# Micro.net
KiCad netlist of a schematic drawn in Altium Designer
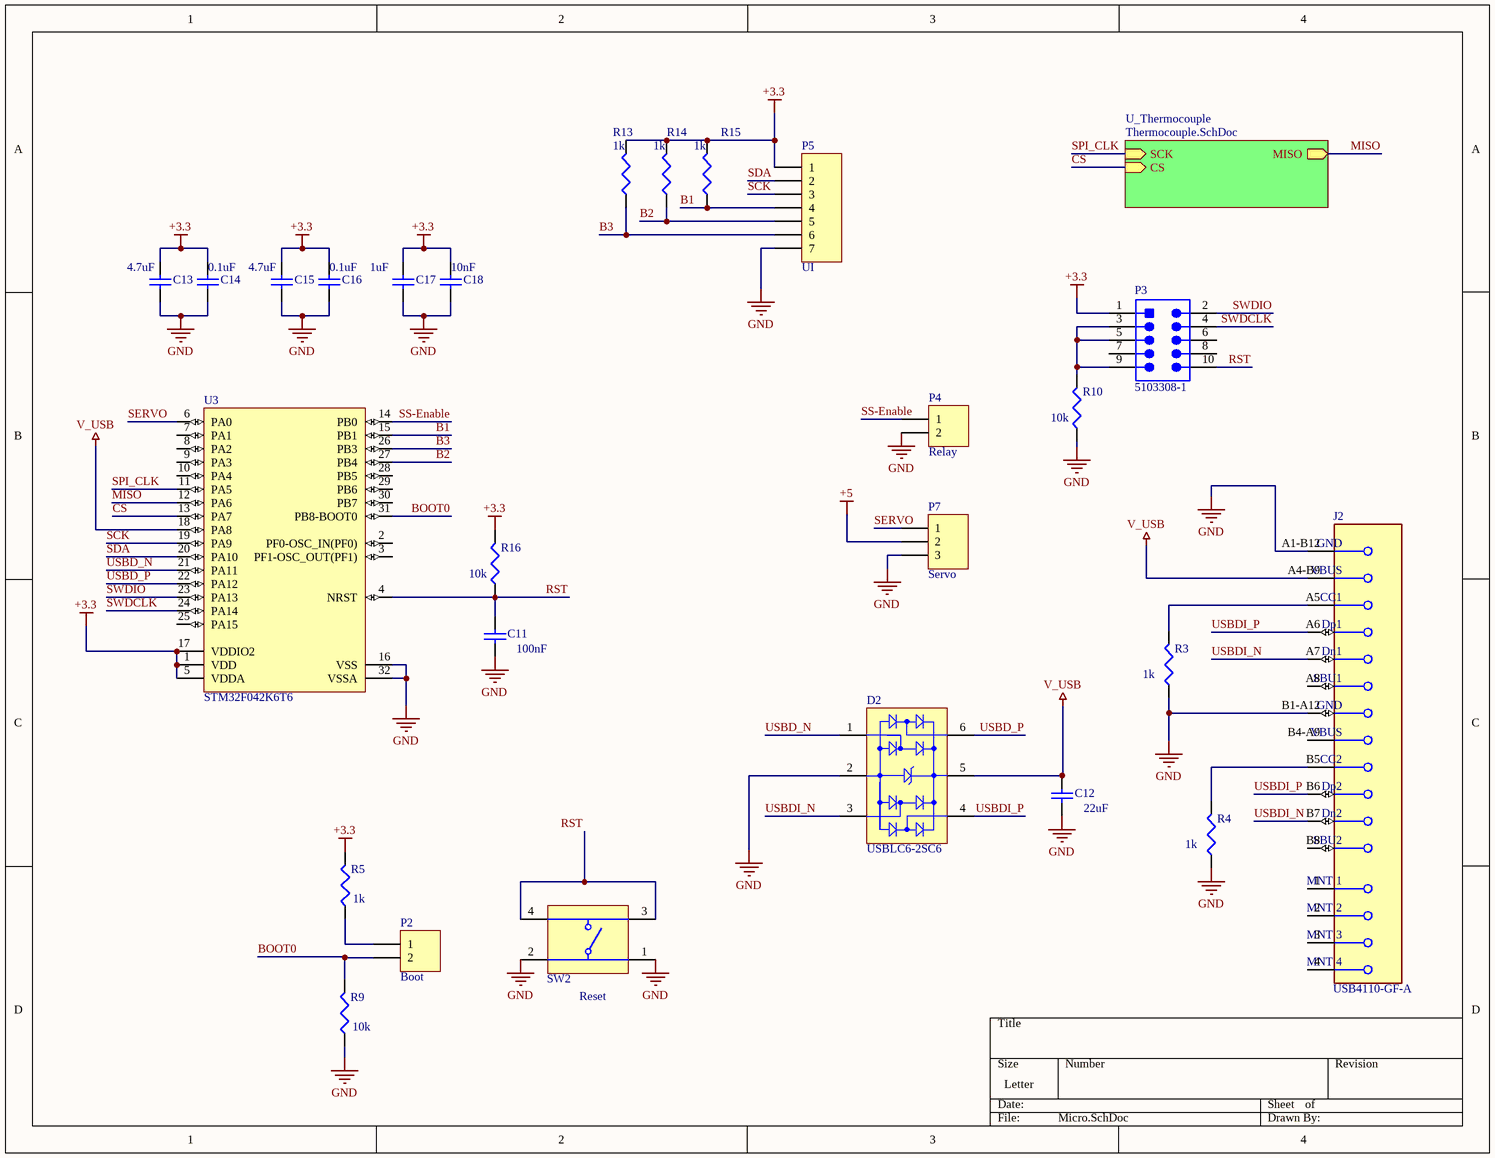
[diagram p0: Micro.SchDoc]

(export (version "E")
  (design (tool "Eeschema 10.0.6"))
  (components
    (comp (ref "C11")
      (value "100nF")
      (footprint "1608[0603]")
      (description "Capacitor (Semiconductor SIM Model)")
      (fields
        (field (name "LCSC PART #") "C14663")
        (field (name "Comment") "Cap Semi")
        (field (name "PUBLISHER") "Altium Limited")
      )
      (libsource (lib "STM32F4_Breakout") (part "Cap Semi_3"))
    )
    (comp (ref "C12")
      (value "22uF")
      (footprint "1608[0603]")
      (description "Capacitor (Semiconductor SIM Model)")
      (fields
        (field (name "LCSC PART #") "C14663")
        (field (name "Comment") "Cap Semi")
        (field (name "PUBLISHER") "Altium Limited")
      )
      (libsource (lib "STM32F4_Breakout") (part "Cap Semi_3"))
    )
    (comp (ref "C13")
      (value "4.7uF")
      (footprint "1608[0603]")
      (description "Capacitor (Semiconductor SIM Model)")
      (fields
        (field (name "LCSC PART #") "C15849")
        (field (name "Comment") "Cap Semi")
        (field (name "PUBLISHER") "Altium Limited")
      )
      (libsource (lib "STM32F4_Breakout") (part "Cap Semi_1"))
    )
    (comp (ref "C14")
      (value "0.1uF")
      (footprint "1608[0603]")
      (description "Capacitor (Semiconductor SIM Model)")
      (fields
        (field (name "LCSC PART #") "C15195")
        (field (name "Comment") "Cap Semi")
        (field (name "PUBLISHER") "Altium Limited")
      )
      (libsource (lib "STM32F4_Breakout") (part "Cap Semi_2"))
    )
    (comp (ref "C15")
      (value "4.7uF")
      (footprint "1608[0603]")
      (description "Capacitor (Semiconductor SIM Model)")
      (fields
        (field (name "LCSC PART #") "C15849")
        (field (name "Comment") "Cap Semi")
        (field (name "PUBLISHER") "Altium Limited")
      )
      (libsource (lib "STM32F4_Breakout") (part "Cap Semi_1"))
    )
    (comp (ref "C16")
      (value "0.1uF")
      (footprint "1608[0603]")
      (description "Capacitor (Semiconductor SIM Model)")
      (fields
        (field (name "LCSC PART #") "C15195")
        (field (name "Comment") "Cap Semi")
        (field (name "PUBLISHER") "Altium Limited")
      )
      (libsource (lib "STM32F4_Breakout") (part "Cap Semi_2"))
    )
    (comp (ref "C17")
      (value "1uF")
      (footprint "1608[0603]")
      (description "Capacitor (Semiconductor SIM Model)")
      (fields
        (field (name "LCSC PART #") "C15849")
        (field (name "Comment") "Cap Semi")
        (field (name "PUBLISHER") "Altium Limited")
      )
      (libsource (lib "STM32F4_Breakout") (part "Cap Semi_1"))
    )
    (comp (ref "C18")
      (value "10nF")
      (footprint "1608[0603]")
      (description "Capacitor (Semiconductor SIM Model)")
      (fields
        (field (name "LCSC PART #") "C15195")
        (field (name "Comment") "Cap Semi")
        (field (name "PUBLISHER") "Altium Limited")
      )
      (libsource (lib "STM32F4_Breakout") (part "Cap Semi_2"))
    )
    (comp (ref "D2")
      (value "USBLC6-2SC6")
      (footprint "STM-SOT23-6L_V")
      (description "Very low capacitance ESD protection, 3.5 pF, -40 to 125 degC, 6-Pin SOT23, RoHS, Tape and Reel")
      (fields (field (name "MANUFACTURER") "STMicroelectronics"))
      (libsource (lib "Altium Content Vault") (part "STM-USB_DVI_HDMIULC6-4SC6X-SOT23-6L"))
    )
    (comp (ref "J2")
      (value "USB4110-GF-A")
      (footprint "FP-USB4110-GF-A-MFG")
      (description "CONN USB 2.0 TYPE-C R/A SMT")
      (fields
        (field (name "OCTOPART") "https://octopart.com/usb4110-gf-a-gct-103941985")
        (field (name "MANUFACTURER") "GCT")
      )
      (libsource (lib "Altium Content Vault") (part "e23f2b38bb3c3f98e683ebab9ede730"))
    )
    (comp (ref "P2")
      (value "Boot")
      (footprint "HDR1X2")
      (description "Header, 2-Pin")
      (fields (field (name "PUBLISHER") "Altium Limited"))
      (libsource (lib "Miscellaneous Connectors") (part "Header 2"))
    )
    (comp (ref "P3")
      (value "5103308-1")
      (footprint "TECO-5103308-1_V")
      (description "Male Header, Pitch 2.54 mm, 2 x 5 Position, Height 9.85 mm, Tail Length 3.05 mm, RoHS, Tube")
      (fields (field (name "MANUFACTURER") "TE Connectivity"))
      (libsource (lib "Altium Content Vault") (part "CN-2P-M-R10"))
    )
    (comp (ref "P4")
      (value "Relay")
      (footprint "HDR1X2H")
      (description "Header, 2-Pin, Right Angle")
      (fields (field (name "PUBLISHER") "Altium Limited"))
      (libsource (lib "Miscellaneous Connectors") (part "Header 2H"))
    )
    (comp (ref "P5")
      (value "UI")
      (footprint "HDR1X7H")
      (description "Header, 7-Pin, Right Angle")
      (fields (field (name "PUBLISHER") "Altium Limited"))
      (libsource (lib "Miscellaneous Connectors") (part "Header 7H"))
    )
    (comp (ref "P7")
      (value "Servo")
      (footprint "HDR1X3H")
      (description "Header, 3-Pin, Right Angle")
      (fields (field (name "PUBLISHER") "Altium Limited"))
      (libsource (lib "Miscellaneous Connectors") (part "Header 3H"))
    )
    (comp (ref "R3")
      (value "1k")
      (footprint "J1-0603")
      (description "Resistor")
      (fields
        (field (name "LCSC PART #") "C25804")
        (field (name "Comment") "Res3")
        (field (name "PUBLISHER") "Altium Limited")
      )
      (libsource (lib "STM32F4_Breakout") (part "Res3_2"))
    )
    (comp (ref "R4")
      (value "1k")
      (footprint "J1-0603")
      (description "Resistor")
      (fields
        (field (name "LCSC PART #") "C25804")
        (field (name "Comment") "Res3")
        (field (name "PUBLISHER") "Altium Limited")
      )
      (libsource (lib "STM32F4_Breakout") (part "Res3_2"))
    )
    (comp (ref "R5")
      (value "1k")
      (footprint "J1-0603")
      (description "Resistor")
      (fields
        (field (name "LCSC PART #") "C25804")
        (field (name "Comment") "Res3")
        (field (name "PUBLISHER") "Altium Limited")
      )
      (libsource (lib "STM32F4_Breakout") (part "Res3_2"))
    )
    (comp (ref "R9")
      (value "10k")
      (footprint "J1-0603")
      (description "Resistor")
      (fields
        (field (name "LCSC PART #") "C25804")
        (field (name "Comment") "Res3")
        (field (name "PUBLISHER") "Altium Limited")
      )
      (libsource (lib "STM32F4_Breakout") (part "Res3_2"))
    )
    (comp (ref "R10")
      (value "10k")
      (footprint "J1-0603")
      (description "Resistor")
      (fields
        (field (name "LCSC PART #") "C25804")
        (field (name "Comment") "Res3")
        (field (name "PUBLISHER") "Altium Limited")
      )
      (libsource (lib "STM32F4_Breakout") (part "Res3_2"))
    )
    (comp (ref "R13")
      (value "1k")
      (footprint "J1-0603")
      (description "Resistor")
      (fields
        (field (name "LCSC PART #") "C25804")
        (field (name "Comment") "Res3")
        (field (name "PUBLISHER") "Altium Limited")
      )
      (libsource (lib "STM32F4_Breakout") (part "Res3_2"))
    )
    (comp (ref "R14")
      (value "1k")
      (footprint "J1-0603")
      (description "Resistor")
      (fields
        (field (name "LCSC PART #") "C25804")
        (field (name "Comment") "Res3")
        (field (name "PUBLISHER") "Altium Limited")
      )
      (libsource (lib "STM32F4_Breakout") (part "Res3_2"))
    )
    (comp (ref "R15")
      (value "1k")
      (footprint "J1-0603")
      (description "Resistor")
      (fields
        (field (name "LCSC PART #") "C25804")
        (field (name "Comment") "Res3")
        (field (name "PUBLISHER") "Altium Limited")
      )
      (libsource (lib "STM32F4_Breakout") (part "Res3_2"))
    )
    (comp (ref "R16")
      (value "10k")
      (footprint "J1-0603")
      (description "Resistor")
      (fields
        (field (name "LCSC PART #") "C25804")
        (field (name "Comment") "Res3")
        (field (name "PUBLISHER") "Altium Limited")
      )
      (libsource (lib "STM32F4_Breakout") (part "Res3_2"))
    )
    (comp (ref "SW2")
      (value "Reset")
      (footprint "CKCP-PTS525SM10SMTR-4_V")
      (description "Microminiature Tact Switch, SPST-NO, 50 mA, 12 VDC, -40 to 60 degC, 4-Pin SMD, RoHS, Tape and Reel")
      (fields (field (name "PART NO") "PTS525SM10SMTRLFS") (field (name "MANUFACTURER") "C&K Components"))
      (libsource (lib "Altium Content Vault") (part "SW-SPST-4_A"))
    )
    (comp (ref "U3")
      (value "STM32F042K6T6")
      (footprint "STM-LQFP32_M")
      (fields (field (name "MANUFACTURER") "STMicroelectronics"))
      (libsource (lib "Altium Content Vault") (part "MC-ARM-STM32F042-LQFP32"))
    )
  )
  (nets
    (net (code "1") (name "+3.3") (class "Default")
      (node (ref "C13") (pin "2") (pinfunction "2_2") (pintype "passive"))
      (node (ref "C14") (pin "2") (pinfunction "2_2") (pintype "passive"))
      (node (ref "C15") (pin "2") (pinfunction "2_2") (pintype "passive"))
      (node (ref "C16") (pin "2") (pinfunction "2_2") (pintype "passive"))
      (node (ref "C17") (pin "2") (pinfunction "2_2") (pintype "passive"))
      (node (ref "C18") (pin "2") (pinfunction "2_2") (pintype "passive"))
      (node (ref "P3") (pin "1") (pinfunction "1_1") (pintype "passive"))
      (node (ref "P5") (pin "1") (pinfunction "1_1") (pintype "passive"))
      (node (ref "R13") (pin "2") (pinfunction "2_2") (pintype "passive"))
      (node (ref "R14") (pin "2") (pinfunction "2_2") (pintype "passive"))
      (node (ref "R15") (pin "2") (pinfunction "2_2") (pintype "passive"))
      (node (ref "R16") (pin "2") (pinfunction "2_2") (pintype "passive"))
      (node (ref "R5") (pin "2") (pinfunction "2_2") (pintype "passive"))
      (node (ref "U3") (pin "1") (pinfunction "VDD_1") (pintype "power_in"))
      (node (ref "U3") (pin "17") (pinfunction "VDDIO2_17") (pintype "power_in"))
      (node (ref "U3") (pin "5") (pinfunction "VDDA_5") (pintype "power_in"))
    )
    (net (code "2") (name "+5") (class "Default")
      (node (ref "P7") (pin "2") (pinfunction "2_2") (pintype "passive"))
    )
    (net (code "3") (name "/B1") (class "Default")
      (node (ref "P5") (pin "4") (pinfunction "4_4") (pintype "passive"))
      (node (ref "R15") (pin "1") (pinfunction "1_1") (pintype "passive"))
      (node (ref "U3") (pin "15") (pinfunction "PB1_15") (pintype "bidirectional"))
    )
    (net (code "4") (name "/B2") (class "Default")
      (node (ref "P5") (pin "5") (pinfunction "5_5") (pintype "passive"))
      (node (ref "R14") (pin "1") (pinfunction "1_1") (pintype "passive"))
      (node (ref "U3") (pin "27") (pinfunction "PB4_27") (pintype "bidirectional"))
    )
    (net (code "5") (name "/B3") (class "Default")
      (node (ref "P5") (pin "6") (pinfunction "6_6") (pintype "passive"))
      (node (ref "R13") (pin "1") (pinfunction "1_1") (pintype "passive"))
      (node (ref "U3") (pin "26") (pinfunction "PB3_26") (pintype "bidirectional"))
    )
    (net (code "6") (name "/BOOT0") (class "Default")
      (node (ref "P2") (pin "2") (pinfunction "2_2") (pintype "passive"))
      (node (ref "R9") (pin "2") (pinfunction "2_2") (pintype "passive"))
      (node (ref "U3") (pin "31") (pinfunction "PB8-BOOT0_31") (pintype "bidirectional"))
    )
    (net (code "7") (name "/CS") (class "Default")
      (node (ref "U3") (pin "13") (pinfunction "PA7_13") (pintype "bidirectional"))
    )
    (net (code "8") (name "/MISO") (class "Default")
      (node (ref "U3") (pin "12") (pinfunction "PA6_12") (pintype "bidirectional"))
    )
    (net (code "9") (name "/RST") (class "Default")
      (node (ref "C11") (pin "2") (pinfunction "2_2") (pintype "passive"))
      (node (ref "P3") (pin "10") (pinfunction "10_10") (pintype "passive"))
      (node (ref "R16") (pin "1") (pinfunction "1_1") (pintype "passive"))
      (node (ref "SW2") (pin "3") (pinfunction "3_3") (pintype "passive"))
      (node (ref "SW2") (pin "4") (pinfunction "4_4") (pintype "passive"))
      (node (ref "U3") (pin "4") (pinfunction "NRST_4") (pintype "bidirectional"))
    )
    (net (code "10") (name "/SCK") (class "Default")
      (node (ref "P5") (pin "3") (pinfunction "3_3") (pintype "passive"))
      (node (ref "U3") (pin "19") (pinfunction "PA9_19") (pintype "bidirectional"))
    )
    (net (code "11") (name "/SDA") (class "Default")
      (node (ref "P5") (pin "2") (pinfunction "2_2") (pintype "passive"))
      (node (ref "U3") (pin "20") (pinfunction "PA10_20") (pintype "bidirectional"))
    )
    (net (code "12") (name "/SERVO") (class "Default")
      (node (ref "P7") (pin "1") (pinfunction "1_1") (pintype "passive"))
      (node (ref "U3") (pin "6") (pinfunction "PA0_6") (pintype "bidirectional"))
    )
    (net (code "13") (name "/SPI_CLK") (class "Default")
      (node (ref "U3") (pin "11") (pinfunction "PA5_11") (pintype "bidirectional"))
    )
    (net (code "14") (name "/SS-Enable") (class "Default")
      (node (ref "P4") (pin "1") (pinfunction "1_1") (pintype "passive"))
      (node (ref "U3") (pin "14") (pinfunction "PB0_14") (pintype "bidirectional"))
    )
    (net (code "15") (name "/SWDCLK") (class "Default")
      (node (ref "P3") (pin "4") (pinfunction "4_4") (pintype "passive"))
      (node (ref "U3") (pin "24") (pinfunction "PA14_24") (pintype "bidirectional"))
    )
    (net (code "16") (name "/SWDIO") (class "Default")
      (node (ref "P3") (pin "2") (pinfunction "2_2") (pintype "passive"))
      (node (ref "U3") (pin "23") (pinfunction "PA13_23") (pintype "bidirectional"))
    )
    (net (code "17") (name "/USBDI_N") (class "Default")
      (node (ref "D2") (pin "3") (pinfunction "I/O_2_3") (pintype "passive"))
      (node (ref "J2") (pin "A7") (pinfunction "Dn1_A7") (pintype "bidirectional"))
      (node (ref "J2") (pin "B7") (pinfunction "Dn2_B7") (pintype "bidirectional"))
    )
    (net (code "18") (name "/USBDI_P") (class "Default")
      (node (ref "D2") (pin "4") (pinfunction "I/O_3_4") (pintype "passive"))
      (node (ref "J2") (pin "A6") (pinfunction "Dp1_A6") (pintype "bidirectional"))
      (node (ref "J2") (pin "B6") (pinfunction "Dp2_B6") (pintype "bidirectional"))
    )
    (net (code "19") (name "/USBD_N") (class "Default")
      (node (ref "D2") (pin "1") (pinfunction "I/O_1_1") (pintype "passive"))
      (node (ref "U3") (pin "21") (pinfunction "PA11_21") (pintype "bidirectional"))
    )
    (net (code "20") (name "/USBD_P") (class "Default")
      (node (ref "D2") (pin "6") (pinfunction "I/O_4_6") (pintype "passive"))
      (node (ref "U3") (pin "22") (pinfunction "PA12_22") (pintype "bidirectional"))
    )
    (net (code "21") (name "GND") (class "Default")
      (node (ref "C11") (pin "1") (pinfunction "1_1") (pintype "passive"))
      (node (ref "C12") (pin "1") (pinfunction "1_1") (pintype "passive"))
      (node (ref "C13") (pin "1") (pinfunction "1_1") (pintype "passive"))
      (node (ref "C14") (pin "1") (pinfunction "1_1") (pintype "passive"))
      (node (ref "C15") (pin "1") (pinfunction "1_1") (pintype "passive"))
      (node (ref "C16") (pin "1") (pinfunction "1_1") (pintype "passive"))
      (node (ref "C17") (pin "1") (pinfunction "1_1") (pintype "passive"))
      (node (ref "C18") (pin "1") (pinfunction "1_1") (pintype "passive"))
      (node (ref "D2") (pin "2") (pinfunction "GND_2") (pintype "passive"))
      (node (ref "J2") (pin "A1-B12") (pinfunction "GND_A1-B12") (pintype "passive"))
      (node (ref "J2") (pin "B1-A12") (pinfunction "GND_B1-A12") (pintype "bidirectional"))
      (node (ref "P4") (pin "2") (pinfunction "2_2") (pintype "passive"))
      (node (ref "P5") (pin "7") (pinfunction "7_7") (pintype "passive"))
      (node (ref "P7") (pin "3") (pinfunction "3_3") (pintype "passive"))
      (node (ref "R10") (pin "1") (pinfunction "1_1") (pintype "passive"))
      (node (ref "R3") (pin "1") (pinfunction "1_1") (pintype "passive"))
      (node (ref "R4") (pin "1") (pinfunction "1_1") (pintype "passive"))
      (node (ref "R9") (pin "1") (pinfunction "1_1") (pintype "passive"))
      (node (ref "SW2") (pin "1") (pinfunction "1_1") (pintype "passive"))
      (node (ref "SW2") (pin "2") (pinfunction "2_2") (pintype "passive"))
      (node (ref "U3") (pin "16") (pinfunction "VSS_16") (pintype "power_in"))
      (node (ref "U3") (pin "32") (pinfunction "VSSA_32") (pintype "power_in"))
    )
    (net (code "22") (name "Net-(J2-CC1)") (class "Default")
      (node (ref "J2") (pin "A5") (pinfunction "CC1_A5") (pintype "power_in"))
      (node (ref "R3") (pin "2") (pinfunction "2_2") (pintype "passive"))
    )
    (net (code "23") (name "Net-(J2-CC2)") (class "Default")
      (node (ref "J2") (pin "B5") (pinfunction "CC2_B5") (pintype "power_in"))
      (node (ref "R4") (pin "2") (pinfunction "2_2") (pintype "passive"))
    )
    (net (code "24") (name "Net-(P2-Pad1)") (class "Default")
      (node (ref "P2") (pin "1") (pinfunction "1_1") (pintype "passive"))
      (node (ref "R5") (pin "1") (pinfunction "1_1") (pintype "passive"))
    )
    (net (code "25") (name "Net-(P3-Pad3)") (class "Default")
      (node (ref "P3") (pin "3") (pinfunction "3_3") (pintype "passive"))
      (node (ref "P3") (pin "5") (pinfunction "5_5") (pintype "passive"))
      (node (ref "P3") (pin "9") (pinfunction "9_9") (pintype "passive"))
      (node (ref "R10") (pin "2") (pinfunction "2_2") (pintype "passive"))
    )
    (net (code "26") (name "V_USB") (class "Default")
      (node (ref "C12") (pin "2") (pinfunction "2_2") (pintype "passive"))
      (node (ref "D2") (pin "5") (pinfunction "VBUS_5") (pintype "passive"))
      (node (ref "J2") (pin "A4-B9") (pinfunction "VBUS_A4-B9") (pintype "power_in"))
      (node (ref "U3") (pin "18") (pinfunction "PA8_18") (pintype "bidirectional"))
    )
    (net (code "27") (name "unconnected-(J2-MNT_1-Pad1)") (class "Default")
      (node (ref "J2") (pin "1") (pinfunction "MNT_1_1") (pintype "passive"))
    )
    (net (code "28") (name "unconnected-(J2-MNT_2-Pad2)") (class "Default")
      (node (ref "J2") (pin "2") (pinfunction "MNT_2_2") (pintype "passive"))
    )
    (net (code "29") (name "unconnected-(J2-MNT_3-Pad3)") (class "Default")
      (node (ref "J2") (pin "3") (pinfunction "MNT_3_3") (pintype "passive"))
    )
    (net (code "30") (name "unconnected-(J2-MNT_4-Pad4)") (class "Default")
      (node (ref "J2") (pin "4") (pinfunction "MNT_4_4") (pintype "passive"))
    )
    (net (code "31") (name "unconnected-(J2-SBU1-PadA8)") (class "Default")
      (node (ref "J2") (pin "A8") (pinfunction "SBU1_A8") (pintype "bidirectional"))
    )
    (net (code "32") (name "unconnected-(J2-SBU2-PadB8)") (class "Default")
      (node (ref "J2") (pin "B8") (pinfunction "SBU2_B8") (pintype "bidirectional"))
    )
    (net (code "33") (name "unconnected-(J2-VBUS-PadB4-A9)") (class "Default")
      (node (ref "J2") (pin "B4-A9") (pinfunction "VBUS_B4-A9") (pintype "power_in"))
    )
    (net (code "34") (name "unconnected-(P3-Pad6)") (class "Default")
      (node (ref "P3") (pin "6") (pinfunction "6_6") (pintype "passive"))
    )
    (net (code "35") (name "unconnected-(P3-Pad7)") (class "Default")
      (node (ref "P3") (pin "7") (pinfunction "7_7") (pintype "passive"))
    )
    (net (code "36") (name "unconnected-(P3-Pad8)") (class "Default")
      (node (ref "P3") (pin "8") (pinfunction "8_8") (pintype "passive"))
    )
    (net (code "37") (name "unconnected-(U3-PA1-Pad7)") (class "Default")
      (node (ref "U3") (pin "7") (pinfunction "PA1_7") (pintype "bidirectional"))
    )
    (net (code "38") (name "unconnected-(U3-PA2-Pad8)") (class "Default")
      (node (ref "U3") (pin "8") (pinfunction "PA2_8") (pintype "bidirectional"))
    )
    (net (code "39") (name "unconnected-(U3-PA3-Pad9)") (class "Default")
      (node (ref "U3") (pin "9") (pinfunction "PA3_9") (pintype "bidirectional"))
    )
    (net (code "40") (name "unconnected-(U3-PA4-Pad10)") (class "Default")
      (node (ref "U3") (pin "10") (pinfunction "PA4_10") (pintype "bidirectional"))
    )
    (net (code "41") (name "unconnected-(U3-PA15-Pad25)") (class "Default")
      (node (ref "U3") (pin "25") (pinfunction "PA15_25") (pintype "bidirectional"))
    )
    (net (code "42") (name "unconnected-(U3-PB5-Pad28)") (class "Default")
      (node (ref "U3") (pin "28") (pinfunction "PB5_28") (pintype "bidirectional"))
    )
    (net (code "43") (name "unconnected-(U3-PB6-Pad29)") (class "Default")
      (node (ref "U3") (pin "29") (pinfunction "PB6_29") (pintype "bidirectional"))
    )
    (net (code "44") (name "unconnected-(U3-PB7-Pad30)") (class "Default")
      (node (ref "U3") (pin "30") (pinfunction "PB7_30") (pintype "bidirectional"))
    )
    (net (code "45") (name "unconnected-(U3-PF0-OSC_IN(PF0)-Pad2)") (class "Default")
      (node (ref "U3") (pin "2") (pinfunction "PF0-OSC_IN(PF0)_2") (pintype "bidirectional"))
    )
    (net (code "46") (name "unconnected-(U3-PF1-OSC_OUT(PF1)-Pad3)") (class "Default")
      (node (ref "U3") (pin "3") (pinfunction "PF1-OSC_OUT(PF1)_3") (pintype "bidirectional"))
    )
  )
)
